# DC_Current.net
KiCad netlist of a schematic drawn in EAGLE
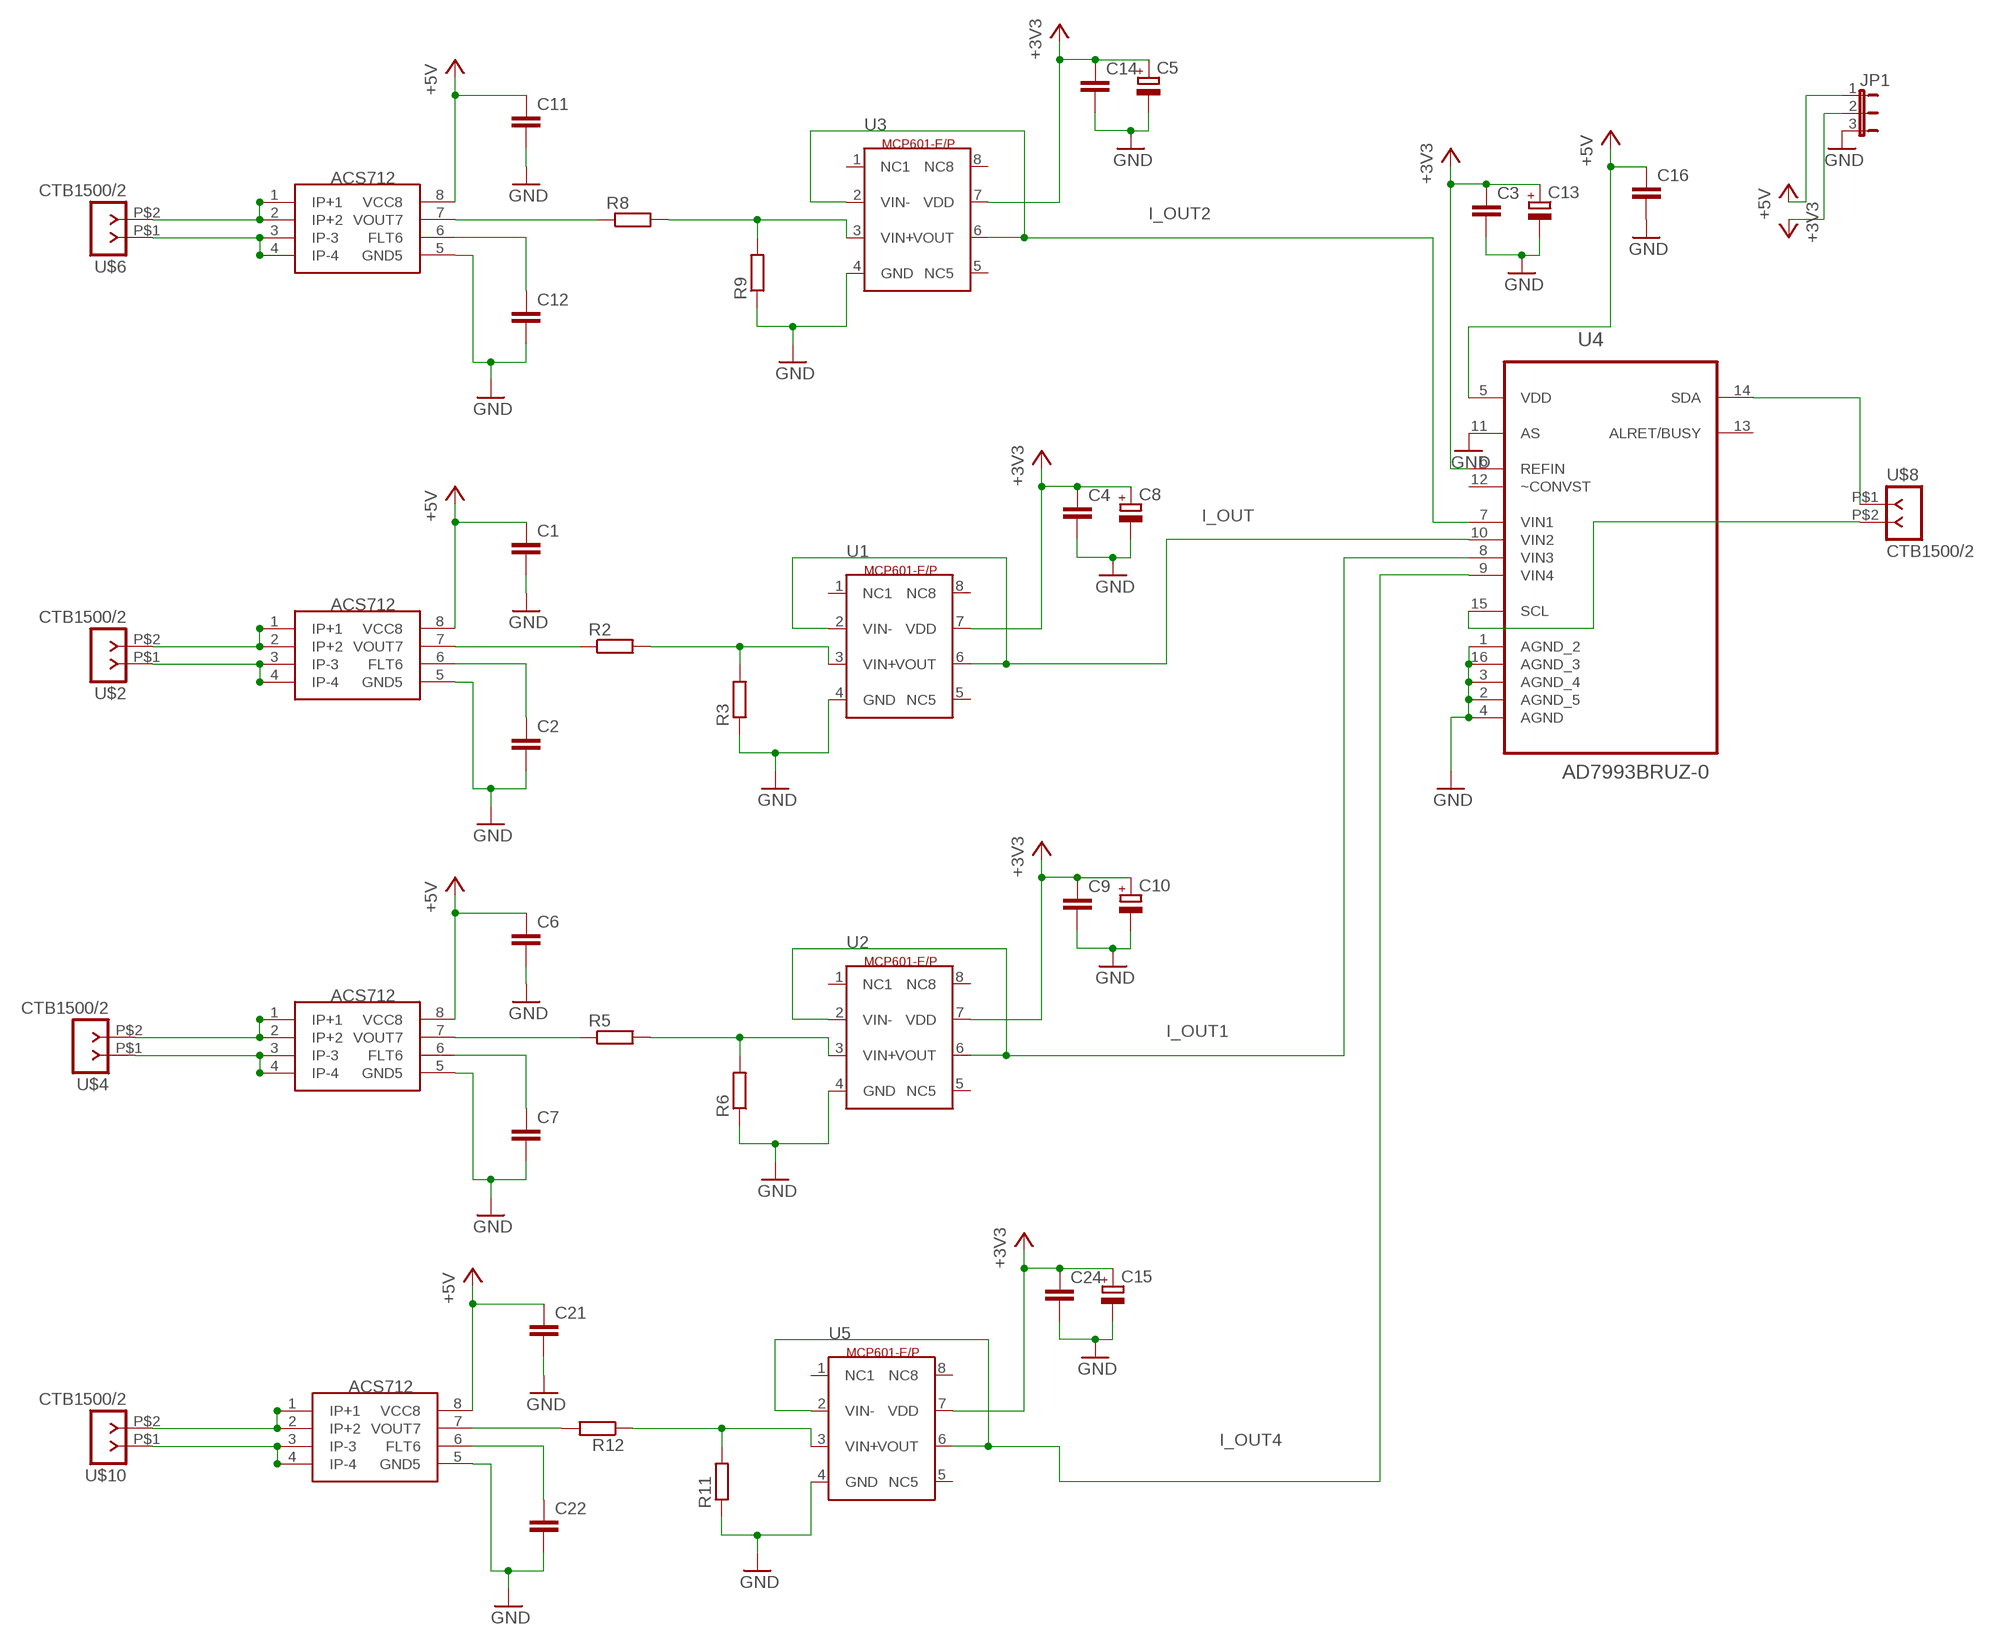
[diagram p0: schematic, sheet 1]

(export (version "E")
  (design (tool "Eeschema 10.0.6"))
  (components
    (comp (ref "C1")
      (value "C-EU025-024X044")
      (footprint "eagle-import:C025-024X044")
      (libsource (lib "eagle-import") (part "C-EU025-024X044"))
    )
    (comp (ref "C2")
      (value "C-EU025-024X044")
      (footprint "eagle-import:C025-024X044")
      (libsource (lib "eagle-import") (part "C-EU025-024X044"))
    )
    (comp (ref "C3")
      (value "C-EU025-024X044")
      (footprint "eagle-import:C025-024X044")
      (libsource (lib "eagle-import") (part "C-EU025-024X044"))
    )
    (comp (ref "C4")
      (value "C-EU025-024X044")
      (footprint "eagle-import:C025-024X044")
      (libsource (lib "eagle-import") (part "C-EU025-024X044"))
    )
    (comp (ref "C5")
      (value "CPOL-EUE2-4")
      (footprint "eagle-import:E2-4")
      (libsource (lib "eagle-import") (part "CPOL-EUE2-4"))
    )
    (comp (ref "C6")
      (value "C-EU025-024X044")
      (footprint "eagle-import:C025-024X044")
      (libsource (lib "eagle-import") (part "C-EU025-024X044"))
    )
    (comp (ref "C7")
      (value "C-EU025-024X044")
      (footprint "eagle-import:C025-024X044")
      (libsource (lib "eagle-import") (part "C-EU025-024X044"))
    )
    (comp (ref "C8")
      (value "CPOL-EUE2-4")
      (footprint "eagle-import:E2-4")
      (libsource (lib "eagle-import") (part "CPOL-EUE2-4"))
    )
    (comp (ref "C9")
      (value "C-EU025-024X044")
      (footprint "eagle-import:C025-024X044")
      (libsource (lib "eagle-import") (part "C-EU025-024X044"))
    )
    (comp (ref "C10")
      (value "CPOL-EUE2-4")
      (footprint "eagle-import:E2-4")
      (libsource (lib "eagle-import") (part "CPOL-EUE2-4"))
    )
    (comp (ref "C11")
      (value "C-EU025-024X044")
      (footprint "eagle-import:C025-024X044")
      (libsource (lib "eagle-import") (part "C-EU025-024X044"))
    )
    (comp (ref "C12")
      (value "C-EU025-024X044")
      (footprint "eagle-import:C025-024X044")
      (libsource (lib "eagle-import") (part "C-EU025-024X044"))
    )
    (comp (ref "C13")
      (value "CPOL-EUE2-4")
      (footprint "eagle-import:E2-4")
      (libsource (lib "eagle-import") (part "CPOL-EUE2-4"))
    )
    (comp (ref "C14")
      (value "C-EU025-024X044")
      (footprint "eagle-import:C025-024X044")
      (libsource (lib "eagle-import") (part "C-EU025-024X044"))
    )
    (comp (ref "C15")
      (value "CPOL-EUE2-4")
      (footprint "eagle-import:E2-4")
      (libsource (lib "eagle-import") (part "CPOL-EUE2-4"))
    )
    (comp (ref "C16")
      (value "C-EU025-025X050")
      (footprint "eagle-import:C025-025X050")
      (libsource (lib "eagle-import") (part "C-EU025-025X050"))
    )
    (comp (ref "C21")
      (value "C-EU025-024X044")
      (footprint "eagle-import:C025-024X044")
      (libsource (lib "eagle-import") (part "C-EU025-024X044"))
    )
    (comp (ref "C22")
      (value "C-EU025-024X044")
      (footprint "eagle-import:C025-024X044")
      (libsource (lib "eagle-import") (part "C-EU025-024X044"))
    )
    (comp (ref "C24")
      (value "C-EU025-024X044")
      (footprint "eagle-import:C025-024X044")
      (libsource (lib "eagle-import") (part "C-EU025-024X044"))
    )
    (comp (ref "JP1")
      (value "JP2E")
      (footprint "eagle-import:JP2")
      (libsource (lib "eagle-import") (part "JP2E"))
    )
    (comp (ref "R2")
      (value "R-EU_0207/7")
      (footprint "eagle-import:0207_7")
      (libsource (lib "eagle-import") (part "R-EU_0207/7"))
    )
    (comp (ref "R3")
      (value "R-EU_0207/7")
      (footprint "eagle-import:0207_7")
      (libsource (lib "eagle-import") (part "R-EU_0207/7"))
    )
    (comp (ref "R5")
      (value "R-EU_0207/7")
      (footprint "eagle-import:0207_7")
      (libsource (lib "eagle-import") (part "R-EU_0207/7"))
    )
    (comp (ref "R6")
      (value "R-EU_0207/7")
      (footprint "eagle-import:0207_7")
      (libsource (lib "eagle-import") (part "R-EU_0207/7"))
    )
    (comp (ref "R8")
      (value "R-EU_0207/7")
      (footprint "eagle-import:0207_7")
      (libsource (lib "eagle-import") (part "R-EU_0207/7"))
    )
    (comp (ref "R9")
      (value "R-EU_0207/7")
      (footprint "eagle-import:0207_7")
      (libsource (lib "eagle-import") (part "R-EU_0207/7"))
    )
    (comp (ref "R11")
      (value "R-EU_0207/7")
      (footprint "eagle-import:0207_7")
      (libsource (lib "eagle-import") (part "R-EU_0207/7"))
    )
    (comp (ref "R12")
      (value "R-EU_0207/7")
      (footprint "eagle-import:0207_7")
      (libsource (lib "eagle-import") (part "R-EU_0207/7"))
    )
    (comp (ref "U$1")
      (value "ACS712")
      (footprint "eagle-import:SO8")
      (libsource (lib "eagle-import") (part "ACS712"))
    )
    (comp (ref "U$2")
      (value "CTB1500/2")
      (footprint "eagle-import:CTB1500-2")
      (libsource (lib "eagle-import") (part "CTB1500/2"))
    )
    (comp (ref "U$3")
      (value "ACS712")
      (footprint "eagle-import:SO8")
      (libsource (lib "eagle-import") (part "ACS712"))
    )
    (comp (ref "U$4")
      (value "CTB1500/2")
      (footprint "eagle-import:CTB1500-2")
      (libsource (lib "eagle-import") (part "CTB1500/2"))
    )
    (comp (ref "U$5")
      (value "ACS712")
      (footprint "eagle-import:SO8")
      (libsource (lib "eagle-import") (part "ACS712"))
    )
    (comp (ref "U$6")
      (value "CTB1500/2")
      (footprint "eagle-import:CTB1500-2")
      (libsource (lib "eagle-import") (part "CTB1500/2"))
    )
    (comp (ref "U$8")
      (value "CTB1500/2")
      (footprint "eagle-import:CTB1500-2")
      (libsource (lib "eagle-import") (part "CTB1500/2"))
    )
    (comp (ref "U$9")
      (value "ACS712")
      (footprint "eagle-import:SO8")
      (libsource (lib "eagle-import") (part "ACS712"))
    )
    (comp (ref "U$10")
      (value "CTB1500/2")
      (footprint "eagle-import:CTB1500-2")
      (libsource (lib "eagle-import") (part "CTB1500/2"))
    )
    (comp (ref "U1")
      (value "MCP601")
      (footprint "eagle-import:SO8")
      (libsource (lib "eagle-import") (part "MCP601"))
    )
    (comp (ref "U2")
      (value "MCP601")
      (footprint "eagle-import:SO8")
      (libsource (lib "eagle-import") (part "MCP601"))
    )
    (comp (ref "U3")
      (value "MCP601")
      (footprint "eagle-import:SO8")
      (libsource (lib "eagle-import") (part "MCP601"))
    )
    (comp (ref "U4")
      (value "AD7993BRUZ-0")
      (footprint "eagle-import:SOP65P640X120-16N")
      (libsource (lib "eagle-import") (part "AD7993BRUZ-0"))
    )
    (comp (ref "U5")
      (value "MCP601")
      (footprint "eagle-import:SO8")
      (libsource (lib "eagle-import") (part "MCP601"))
    )
  )
  (nets
    (net (code "1") (name "+3V3") (class "Default")
      (node (ref "C10") (pin "+") (pinfunction "+_+") (pintype "passive"))
      (node (ref "C13") (pin "+") (pinfunction "+_+") (pintype "passive"))
      (node (ref "C14") (pin "1") (pinfunction "1_1") (pintype "passive"))
      (node (ref "C15") (pin "+") (pinfunction "+_+") (pintype "passive"))
      (node (ref "C24") (pin "1") (pinfunction "1_1") (pintype "passive"))
      (node (ref "C3") (pin "1") (pinfunction "1_1") (pintype "passive"))
      (node (ref "C4") (pin "1") (pinfunction "1_1") (pintype "passive"))
      (node (ref "C5") (pin "+") (pinfunction "+_+") (pintype "passive"))
      (node (ref "C8") (pin "+") (pinfunction "+_+") (pintype "passive"))
      (node (ref "C9") (pin "1") (pinfunction "1_1") (pintype "passive"))
      (node (ref "JP1") (pin "2") (pinfunction "2_2") (pintype "passive"))
      (node (ref "U1") (pin "7") (pinfunction "VDD_7") (pintype "power_in"))
      (node (ref "U2") (pin "7") (pinfunction "VDD_7") (pintype "power_in"))
      (node (ref "U3") (pin "7") (pinfunction "VDD_7") (pintype "power_in"))
      (node (ref "U4") (pin "6") (pinfunction "REFIN_6") (pintype "input"))
      (node (ref "U5") (pin "7") (pinfunction "VDD_7") (pintype "power_in"))
    )
    (net (code "2") (name "+5V") (class "Default")
      (node (ref "C1") (pin "1") (pinfunction "1_1") (pintype "passive"))
      (node (ref "C11") (pin "1") (pinfunction "1_1") (pintype "passive"))
      (node (ref "C16") (pin "1") (pinfunction "1_1") (pintype "passive"))
      (node (ref "C21") (pin "1") (pinfunction "1_1") (pintype "passive"))
      (node (ref "C6") (pin "1") (pinfunction "1_1") (pintype "passive"))
      (node (ref "JP1") (pin "1") (pinfunction "1_1") (pintype "passive"))
      (node (ref "U$1") (pin "8") (pinfunction "VCC8_8") (pintype "power_in"))
      (node (ref "U$3") (pin "8") (pinfunction "VCC8_8") (pintype "power_in"))
      (node (ref "U$5") (pin "8") (pinfunction "VCC8_8") (pintype "power_in"))
      (node (ref "U$9") (pin "8") (pinfunction "VCC8_8") (pintype "power_in"))
      (node (ref "U4") (pin "5") (pinfunction "VDD_5") (pintype "power_in"))
    )
    (net (code "3") (name "/I_OUT") (class "Default")
      (node (ref "U1") (pin "2") (pinfunction "VIN-_2") (pintype "bidirectional"))
      (node (ref "U1") (pin "6") (pinfunction "VOUT_6") (pintype "bidirectional"))
      (node (ref "U4") (pin "10") (pinfunction "VIN2_10") (pintype "input"))
    )
    (net (code "4") (name "/I_OUT1") (class "Default")
      (node (ref "U2") (pin "2") (pinfunction "VIN-_2") (pintype "bidirectional"))
      (node (ref "U2") (pin "6") (pinfunction "VOUT_6") (pintype "bidirectional"))
      (node (ref "U4") (pin "8") (pinfunction "VIN3_8") (pintype "input"))
    )
    (net (code "5") (name "/I_OUT2") (class "Default")
      (node (ref "U3") (pin "2") (pinfunction "VIN-_2") (pintype "bidirectional"))
      (node (ref "U3") (pin "6") (pinfunction "VOUT_6") (pintype "bidirectional"))
      (node (ref "U4") (pin "7") (pinfunction "VIN1_7") (pintype "input"))
    )
    (net (code "6") (name "/I_OUT4") (class "Default")
      (node (ref "U4") (pin "9") (pinfunction "VIN4_9") (pintype "input"))
      (node (ref "U5") (pin "2") (pinfunction "VIN-_2") (pintype "bidirectional"))
      (node (ref "U5") (pin "6") (pinfunction "VOUT_6") (pintype "bidirectional"))
    )
    (net (code "7") (name "GND") (class "Default")
      (node (ref "C1") (pin "2") (pinfunction "2_2") (pintype "passive"))
      (node (ref "C10") (pin "-") (pinfunction "-_-") (pintype "passive"))
      (node (ref "C11") (pin "2") (pinfunction "2_2") (pintype "passive"))
      (node (ref "C12") (pin "2") (pinfunction "2_2") (pintype "passive"))
      (node (ref "C13") (pin "-") (pinfunction "-_-") (pintype "passive"))
      (node (ref "C14") (pin "2") (pinfunction "2_2") (pintype "passive"))
      (node (ref "C15") (pin "-") (pinfunction "-_-") (pintype "passive"))
      (node (ref "C16") (pin "2") (pinfunction "2_2") (pintype "passive"))
      (node (ref "C2") (pin "2") (pinfunction "2_2") (pintype "passive"))
      (node (ref "C21") (pin "2") (pinfunction "2_2") (pintype "passive"))
      (node (ref "C22") (pin "2") (pinfunction "2_2") (pintype "passive"))
      (node (ref "C24") (pin "2") (pinfunction "2_2") (pintype "passive"))
      (node (ref "C3") (pin "2") (pinfunction "2_2") (pintype "passive"))
      (node (ref "C4") (pin "2") (pinfunction "2_2") (pintype "passive"))
      (node (ref "C5") (pin "-") (pinfunction "-_-") (pintype "passive"))
      (node (ref "C6") (pin "2") (pinfunction "2_2") (pintype "passive"))
      (node (ref "C7") (pin "2") (pinfunction "2_2") (pintype "passive"))
      (node (ref "C8") (pin "-") (pinfunction "-_-") (pintype "passive"))
      (node (ref "C9") (pin "2") (pinfunction "2_2") (pintype "passive"))
      (node (ref "JP1") (pin "3") (pinfunction "3_3") (pintype "passive"))
      (node (ref "R11") (pin "1") (pinfunction "1_1") (pintype "passive"))
      (node (ref "R3") (pin "1") (pinfunction "1_1") (pintype "passive"))
      (node (ref "R6") (pin "1") (pinfunction "1_1") (pintype "passive"))
      (node (ref "R9") (pin "1") (pinfunction "1_1") (pintype "passive"))
      (node (ref "U$1") (pin "5") (pinfunction "GND5_5") (pintype "power_in"))
      (node (ref "U$3") (pin "5") (pinfunction "GND5_5") (pintype "power_in"))
      (node (ref "U$5") (pin "5") (pinfunction "GND5_5") (pintype "power_in"))
      (node (ref "U$9") (pin "5") (pinfunction "GND5_5") (pintype "power_in"))
      (node (ref "U1") (pin "4") (pinfunction "GND_4") (pintype "power_in"))
      (node (ref "U2") (pin "4") (pinfunction "GND_4") (pintype "power_in"))
      (node (ref "U3") (pin "4") (pinfunction "GND_4") (pintype "power_in"))
      (node (ref "U4") (pin "1") (pinfunction "AGND_2_1") (pintype "passive"))
      (node (ref "U4") (pin "11") (pinfunction "AS_11") (pintype "input"))
      (node (ref "U4") (pin "16") (pinfunction "AGND_3_16") (pintype "passive"))
      (node (ref "U4") (pin "2") (pinfunction "AGND_5_2") (pintype "passive"))
      (node (ref "U4") (pin "3") (pinfunction "AGND_4_3") (pintype "passive"))
      (node (ref "U4") (pin "4") (pinfunction "AGND_4") (pintype "passive"))
      (node (ref "U5") (pin "4") (pinfunction "GND_4") (pintype "power_in"))
    )
    (net (code "8") (name "Net-(U$1-FLT6)") (class "Default")
      (node (ref "C2") (pin "1") (pinfunction "1_1") (pintype "passive"))
      (node (ref "U$1") (pin "6") (pinfunction "FLT6_6") (pintype "passive"))
    )
    (net (code "9") (name "Net-(U$1-IP+1)") (class "Default")
      (node (ref "U$1") (pin "1") (pinfunction "IP+1_1") (pintype "bidirectional"))
      (node (ref "U$1") (pin "2") (pinfunction "IP+2_2") (pintype "bidirectional"))
      (node (ref "U$2") (pin "P$2") (pinfunction "2_P$2") (pintype "passive"))
    )
    (net (code "10") (name "Net-(U$1-IP-3)") (class "Default")
      (node (ref "U$1") (pin "3") (pinfunction "IP-3_3") (pintype "bidirectional"))
      (node (ref "U$1") (pin "4") (pinfunction "IP-4_4") (pintype "bidirectional"))
      (node (ref "U$2") (pin "P$1") (pinfunction "1_P$1") (pintype "passive"))
    )
    (net (code "11") (name "Net-(U$1-VOUT7)") (class "Default")
      (node (ref "R2") (pin "1") (pinfunction "1_1") (pintype "passive"))
      (node (ref "U$1") (pin "7") (pinfunction "VOUT7_7") (pintype "output"))
    )
    (net (code "12") (name "Net-(U$3-FLT6)") (class "Default")
      (node (ref "C7") (pin "1") (pinfunction "1_1") (pintype "passive"))
      (node (ref "U$3") (pin "6") (pinfunction "FLT6_6") (pintype "passive"))
    )
    (net (code "13") (name "Net-(U$3-IP+1)") (class "Default")
      (node (ref "U$3") (pin "1") (pinfunction "IP+1_1") (pintype "bidirectional"))
      (node (ref "U$3") (pin "2") (pinfunction "IP+2_2") (pintype "bidirectional"))
      (node (ref "U$4") (pin "P$2") (pinfunction "2_P$2") (pintype "passive"))
    )
    (net (code "14") (name "Net-(U$3-IP-3)") (class "Default")
      (node (ref "U$3") (pin "3") (pinfunction "IP-3_3") (pintype "bidirectional"))
      (node (ref "U$3") (pin "4") (pinfunction "IP-4_4") (pintype "bidirectional"))
      (node (ref "U$4") (pin "P$1") (pinfunction "1_P$1") (pintype "passive"))
    )
    (net (code "15") (name "Net-(U$3-VOUT7)") (class "Default")
      (node (ref "R5") (pin "1") (pinfunction "1_1") (pintype "passive"))
      (node (ref "U$3") (pin "7") (pinfunction "VOUT7_7") (pintype "output"))
    )
    (net (code "16") (name "Net-(U$5-FLT6)") (class "Default")
      (node (ref "C12") (pin "1") (pinfunction "1_1") (pintype "passive"))
      (node (ref "U$5") (pin "6") (pinfunction "FLT6_6") (pintype "passive"))
    )
    (net (code "17") (name "Net-(U$5-IP+1)") (class "Default")
      (node (ref "U$5") (pin "1") (pinfunction "IP+1_1") (pintype "bidirectional"))
      (node (ref "U$5") (pin "2") (pinfunction "IP+2_2") (pintype "bidirectional"))
      (node (ref "U$6") (pin "P$2") (pinfunction "2_P$2") (pintype "passive"))
    )
    (net (code "18") (name "Net-(U$5-IP-3)") (class "Default")
      (node (ref "U$5") (pin "3") (pinfunction "IP-3_3") (pintype "bidirectional"))
      (node (ref "U$5") (pin "4") (pinfunction "IP-4_4") (pintype "bidirectional"))
      (node (ref "U$6") (pin "P$1") (pinfunction "1_P$1") (pintype "passive"))
    )
    (net (code "19") (name "Net-(U$5-VOUT7)") (class "Default")
      (node (ref "R8") (pin "1") (pinfunction "1_1") (pintype "passive"))
      (node (ref "U$5") (pin "7") (pinfunction "VOUT7_7") (pintype "output"))
    )
    (net (code "20") (name "Net-(U$8-1)") (class "Default")
      (node (ref "U$8") (pin "P$1") (pinfunction "1_P$1") (pintype "passive"))
      (node (ref "U4") (pin "14") (pinfunction "SDA_14") (pintype "bidirectional"))
    )
    (net (code "21") (name "Net-(U$8-2)") (class "Default")
      (node (ref "U$8") (pin "P$2") (pinfunction "2_P$2") (pintype "passive"))
      (node (ref "U4") (pin "15") (pinfunction "SCL_15") (pintype "input"))
    )
    (net (code "22") (name "Net-(U$9-FLT6)") (class "Default")
      (node (ref "C22") (pin "1") (pinfunction "1_1") (pintype "passive"))
      (node (ref "U$9") (pin "6") (pinfunction "FLT6_6") (pintype "passive"))
    )
    (net (code "23") (name "Net-(U$9-VOUT7)") (class "Default")
      (node (ref "R12") (pin "2") (pinfunction "2_2") (pintype "passive"))
      (node (ref "U$9") (pin "7") (pinfunction "VOUT7_7") (pintype "output"))
    )
    (net (code "24") (name "Net-(U$10-1)") (class "Default")
      (node (ref "U$10") (pin "P$1") (pinfunction "1_P$1") (pintype "passive"))
      (node (ref "U$9") (pin "3") (pinfunction "IP-3_3") (pintype "bidirectional"))
      (node (ref "U$9") (pin "4") (pinfunction "IP-4_4") (pintype "bidirectional"))
    )
    (net (code "25") (name "Net-(U$10-2)") (class "Default")
      (node (ref "U$10") (pin "P$2") (pinfunction "2_P$2") (pintype "passive"))
      (node (ref "U$9") (pin "1") (pinfunction "IP+1_1") (pintype "bidirectional"))
      (node (ref "U$9") (pin "2") (pinfunction "IP+2_2") (pintype "bidirectional"))
    )
    (net (code "26") (name "Net-(U1-VIN+)") (class "Default")
      (node (ref "R2") (pin "2") (pinfunction "2_2") (pintype "passive"))
      (node (ref "R3") (pin "2") (pinfunction "2_2") (pintype "passive"))
      (node (ref "U1") (pin "3") (pinfunction "VIN+_3") (pintype "bidirectional"))
    )
    (net (code "27") (name "Net-(U2-VIN+)") (class "Default")
      (node (ref "R5") (pin "2") (pinfunction "2_2") (pintype "passive"))
      (node (ref "R6") (pin "2") (pinfunction "2_2") (pintype "passive"))
      (node (ref "U2") (pin "3") (pinfunction "VIN+_3") (pintype "bidirectional"))
    )
    (net (code "28") (name "Net-(U3-VIN+)") (class "Default")
      (node (ref "R8") (pin "2") (pinfunction "2_2") (pintype "passive"))
      (node (ref "R9") (pin "2") (pinfunction "2_2") (pintype "passive"))
      (node (ref "U3") (pin "3") (pinfunction "VIN+_3") (pintype "bidirectional"))
    )
    (net (code "29") (name "Net-(U5-VIN+)") (class "Default")
      (node (ref "R11") (pin "2") (pinfunction "2_2") (pintype "passive"))
      (node (ref "R12") (pin "1") (pinfunction "1_1") (pintype "passive"))
      (node (ref "U5") (pin "3") (pinfunction "VIN+_3") (pintype "bidirectional"))
    )
    (net (code "30") (name "unconnected-(U1-NC1-Pad1)") (class "Default")
      (node (ref "U1") (pin "1") (pinfunction "NC1_1") (pintype "no_connect"))
    )
    (net (code "31") (name "unconnected-(U1-NC5-Pad5)") (class "Default")
      (node (ref "U1") (pin "5") (pinfunction "NC5_5") (pintype "no_connect"))
    )
    (net (code "32") (name "unconnected-(U1-NC8-Pad8)") (class "Default")
      (node (ref "U1") (pin "8") (pinfunction "NC8_8") (pintype "no_connect"))
    )
    (net (code "33") (name "unconnected-(U2-NC1-Pad1)") (class "Default")
      (node (ref "U2") (pin "1") (pinfunction "NC1_1") (pintype "no_connect"))
    )
    (net (code "34") (name "unconnected-(U2-NC5-Pad5)") (class "Default")
      (node (ref "U2") (pin "5") (pinfunction "NC5_5") (pintype "no_connect"))
    )
    (net (code "35") (name "unconnected-(U2-NC8-Pad8)") (class "Default")
      (node (ref "U2") (pin "8") (pinfunction "NC8_8") (pintype "no_connect"))
    )
    (net (code "36") (name "unconnected-(U3-NC1-Pad1)") (class "Default")
      (node (ref "U3") (pin "1") (pinfunction "NC1_1") (pintype "no_connect"))
    )
    (net (code "37") (name "unconnected-(U3-NC5-Pad5)") (class "Default")
      (node (ref "U3") (pin "5") (pinfunction "NC5_5") (pintype "no_connect"))
    )
    (net (code "38") (name "unconnected-(U3-NC8-Pad8)") (class "Default")
      (node (ref "U3") (pin "8") (pinfunction "NC8_8") (pintype "no_connect"))
    )
    (net (code "39") (name "unconnected-(U4-ALRET{slash}BUSY-Pad13)") (class "Default")
      (node (ref "U4") (pin "13") (pinfunction "ALRET/BUSY_13") (pintype "output"))
    )
    (net (code "40") (name "unconnected-(U4-~{CONVST}-Pad12)") (class "Default")
      (node (ref "U4") (pin "12") (pinfunction "~{CONVST}_12") (pintype "input"))
    )
    (net (code "41") (name "unconnected-(U5-NC1-Pad1)") (class "Default")
      (node (ref "U5") (pin "1") (pinfunction "NC1_1") (pintype "no_connect"))
    )
    (net (code "42") (name "unconnected-(U5-NC5-Pad5)") (class "Default")
      (node (ref "U5") (pin "5") (pinfunction "NC5_5") (pintype "no_connect"))
    )
    (net (code "43") (name "unconnected-(U5-NC8-Pad8)") (class "Default")
      (node (ref "U5") (pin "8") (pinfunction "NC8_8") (pintype "no_connect"))
    )
  )
)
